# GSM.net
KiCad netlist of a schematic drawn in Altium Designer
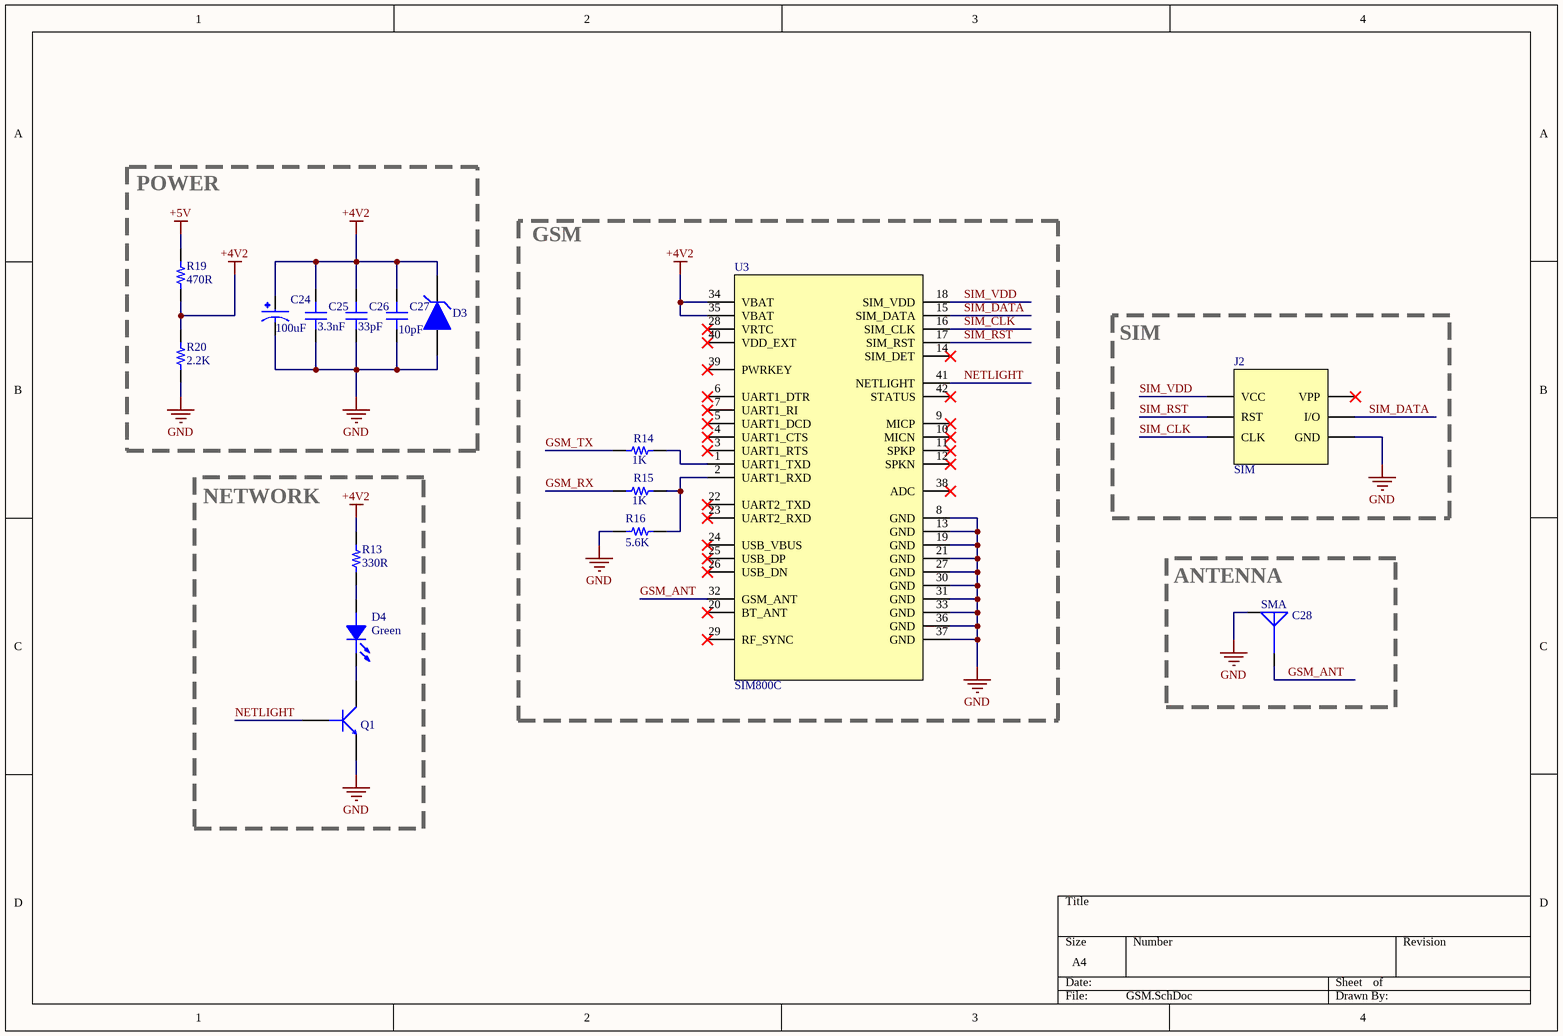
[diagram p0: GSM.SchDoc]

(export (version "E")
  (design (tool "Eeschema 10.0.6"))
  (components
    (comp (ref "C24")
      (value "100uF")
      (footprint "TANTAL B-CASE")
      (description "TANTAL")
      (libsource (lib "hava_kalitesi_olcumu") (part "100uF"))
    )
    (comp (ref "C25")
      (value "3.3nF")
      (footprint "CAP 0603_1608")
      (description "CERAMİC 1206 SMD")
      (libsource (lib "hava_kalitesi_olcumu") (part "3.3nF"))
    )
    (comp (ref "C26")
      (value "33pF")
      (footprint "CAP 0603_1608")
      (description "CERAMİC 1206 SMD")
      (libsource (lib "hava_kalitesi_olcumu") (part "33pF"))
    )
    (comp (ref "C27")
      (value "10pF")
      (footprint "CAP 0603_1608")
      (description "CERAMİC 1206 SMD")
      (libsource (lib "hava_kalitesi_olcumu") (part "10pF"))
    )
    (comp (ref "C28")
      (value "SMA")
      (footprint "CONSMA002-G")
      (description "SMA Anten Connector")
      (libsource (lib "hava_kalitesi_olcumu") (part "Anten SMA"))
    )
    (comp (ref "D3")
      (value "ZENER DIODE")
      (footprint "SOD123")
      (description "SOD123")
      (fields
        (field (name "MANUFACTURER") "ON Semiconductor")
        (field (name "MANUFACTURER PART NUMBER") "1SMB5919BT3G")
      )
      (libsource (lib "hava_kalitesi_olcumu") (part "ZENER DIODE"))
    )
    (comp (ref "D4")
      (value "Green")
      (footprint "0805 Green LED")
      (fields
        (field (name "MANUFACTURER") "AVAGO Technologies")
        (field (name "VOLTAGE") "2.2V")
        (field (name "Comment") "0805 Green LED")
      )
      (libsource (lib "hava_kalitesi_olcumu") (part "0805 Green LED"))
    )
    (comp (ref "J2")
      (value "SIM")
      (footprint "GCT_SIM7100-6-1-15-00-A_REVC")
      (description "Memory Card Connectors Micro SIM Card Connector - Push-Push Type, 6 Pin, SMT, 1.50mm Profile")
      (fields (field (name "MP") "SIM7100-6-1-15-00-A") (field (name "MF") "Global Connector Technology"))
      (libsource (lib "hava_kalitesi_olcumu") (part "SIM7100-6-1-15-00-A"))
    )
    (comp (ref "Q1")
      (value "MMBT3904-7-F")
      (footprint "SOT-23F")
      (description "Transistor General Purpose BJT NPN 40 Volt 0.2A Automotive 3-Pin SOT-23")
      (fields (field (name "MANUFACTURER") "Diodes Zetex") (field (name "DESIGNED BY") "BERK"))
      (libsource (lib "hava_kalitesi_olcumu") (part "MMBT3904-7-F"))
    )
    (comp (ref "R13")
      (value "330R")
      (footprint "RES 0603_1608")
      (description "SMT RES 1206")
      (libsource (lib "hava_kalitesi_olcumu") (part "330R"))
    )
    (comp (ref "R14")
      (value "1K")
      (footprint "RES 0603_1608")
      (description "SMT RES 1206")
      (libsource (lib "hava_kalitesi_olcumu") (part "1K"))
    )
    (comp (ref "R15")
      (value "1K")
      (footprint "RES 0603_1608")
      (description "SMT RES 1206")
      (libsource (lib "hava_kalitesi_olcumu") (part "1K"))
    )
    (comp (ref "R16")
      (value "5.6K")
      (footprint "RES 0603_1608")
      (description "SMT RES 1206")
      (libsource (lib "hava_kalitesi_olcumu") (part "5.6K"))
    )
    (comp (ref "R19")
      (value "470R")
      (footprint "RES 0603_1608")
      (description "SMT RES 1206")
      (libsource (lib "hava_kalitesi_olcumu") (part "470R"))
    )
    (comp (ref "R20")
      (value "2.2K")
      (footprint "RES 0603_1608")
      (description "SMT RES 1206")
      (libsource (lib "hava_kalitesi_olcumu") (part "2.2K"))
    )
    (comp (ref "U3")
      (value "SIM800C")
      (footprint "LCC110P1570X1760X250-42N")
      (description "GSM/Bluetooth")
      (libsource (lib "hava_kalitesi_olcumu") (part "SIM800C"))
    )
  )
  (nets
    (net (code "1") (name "+4V2") (class "Default")
      (node (ref "C24") (pin "+") (pinfunction "+_+") (pintype "passive"))
      (node (ref "C25") (pin "2") (pinfunction "2_2") (pintype "passive"))
      (node (ref "C26") (pin "2") (pinfunction "2_2") (pintype "passive"))
      (node (ref "C27") (pin "2") (pinfunction "2_2") (pintype "passive"))
      (node (ref "D3") (pin "C") (pinfunction "C_C") (pintype "passive"))
      (node (ref "R13") (pin "2") (pinfunction "2_2") (pintype "passive"))
      (node (ref "R19") (pin "1") (pinfunction "1_1") (pintype "passive"))
      (node (ref "R20") (pin "2") (pinfunction "2_2") (pintype "passive"))
      (node (ref "U3") (pin "34") (pinfunction "VBAT_34") (pintype "power_in"))
      (node (ref "U3") (pin "35") (pinfunction "VBAT_35") (pintype "power_in"))
    )
    (net (code "2") (name "+5V") (class "Default")
      (node (ref "R19") (pin "2") (pinfunction "2_2") (pintype "passive"))
    )
    (net (code "3") (name "/GSM_ANT") (class "Default")
      (node (ref "C28") (pin "S") (pinfunction "S_S") (pintype "passive"))
      (node (ref "U3") (pin "32") (pinfunction "GSM_ANT_32") (pintype "power_in"))
    )
    (net (code "4") (name "/GSM_RX") (class "Default")
      (node (ref "R15") (pin "1") (pinfunction "1_1") (pintype "passive"))
    )
    (net (code "5") (name "/GSM_TX") (class "Default")
      (node (ref "R14") (pin "1") (pinfunction "1_1") (pintype "passive"))
    )
    (net (code "6") (name "/NETLIGHT") (class "Default")
      (node (ref "Q1") (pin "1") (pinfunction "B_1") (pintype "power_in"))
      (node (ref "U3") (pin "41") (pinfunction "NETLIGHT_41") (pintype "power_in"))
    )
    (net (code "7") (name "/SIM_CLK") (class "Default")
      (node (ref "J2") (pin "C3") (pinfunction "CLK_C3") (pintype "power_in"))
      (node (ref "U3") (pin "16") (pinfunction "SIM_CLK_16") (pintype "power_in"))
    )
    (net (code "8") (name "/SIM_DATA") (class "Default")
      (node (ref "J2") (pin "C7") (pinfunction "I/O_C7") (pintype "power_in"))
      (node (ref "U3") (pin "15") (pinfunction "SIM_DATA_15") (pintype "power_in"))
    )
    (net (code "9") (name "/SIM_RST") (class "Default")
      (node (ref "J2") (pin "C2") (pinfunction "RST_C2") (pintype "power_in"))
      (node (ref "U3") (pin "17") (pinfunction "SIM_RST_17") (pintype "power_in"))
    )
    (net (code "10") (name "/SIM_VDD") (class "Default")
      (node (ref "J2") (pin "C1") (pinfunction "VCC_C1") (pintype "power_in"))
      (node (ref "U3") (pin "18") (pinfunction "SIM_VDD_18") (pintype "power_in"))
    )
    (net (code "11") (name "GND") (class "Default")
      (node (ref "C24") (pin "-") (pinfunction "-_-") (pintype "passive"))
      (node (ref "C25") (pin "1") (pinfunction "1_1") (pintype "passive"))
      (node (ref "C26") (pin "1") (pinfunction "1_1") (pintype "passive"))
      (node (ref "C27") (pin "1") (pinfunction "1_1") (pintype "passive"))
      (node (ref "C28") (pin "G") (pinfunction "G_G") (pintype "passive"))
      (node (ref "D3") (pin "A") (pinfunction "A_A") (pintype "passive"))
      (node (ref "J2") (pin "C5") (pinfunction "GND_C5") (pintype "power_in"))
      (node (ref "Q1") (pin "2") (pinfunction "E_2") (pintype "power_in"))
      (node (ref "R16") (pin "1") (pinfunction "1_1") (pintype "passive"))
      (node (ref "R20") (pin "1") (pinfunction "1_1") (pintype "passive"))
      (node (ref "U3") (pin "13") (pinfunction "GND_13") (pintype "power_in"))
      (node (ref "U3") (pin "19") (pinfunction "GND_19") (pintype "power_in"))
      (node (ref "U3") (pin "21") (pinfunction "GND_21") (pintype "power_in"))
      (node (ref "U3") (pin "27") (pinfunction "GND_27") (pintype "power_in"))
      (node (ref "U3") (pin "30") (pinfunction "GND_30") (pintype "power_in"))
      (node (ref "U3") (pin "31") (pinfunction "GND_31") (pintype "power_in"))
      (node (ref "U3") (pin "33") (pinfunction "GND_33") (pintype "power_in"))
      (node (ref "U3") (pin "36") (pinfunction "GND_36") (pintype "power_in"))
      (node (ref "U3") (pin "37") (pinfunction "GND_37") (pintype "power_in"))
      (node (ref "U3") (pin "8") (pinfunction "GND_8") (pintype "power_in"))
    )
    (net (code "12") (name "Net-(D4-ANODE)") (class "Default")
      (node (ref "D4") (pin "1") (pinfunction "ANODE_1") (pintype "passive"))
      (node (ref "R13") (pin "1") (pinfunction "1_1") (pintype "passive"))
    )
    (net (code "13") (name "Net-(D4-CATHODE)") (class "Default")
      (node (ref "D4") (pin "2") (pinfunction "CATHODE_2") (pintype "passive"))
      (node (ref "Q1") (pin "3") (pinfunction "C_3") (pintype "power_in"))
    )
    (net (code "14") (name "Net-(U3-UART1_RXD)") (class "Default")
      (node (ref "R15") (pin "2") (pinfunction "2_2") (pintype "passive"))
      (node (ref "R16") (pin "2") (pinfunction "2_2") (pintype "passive"))
      (node (ref "U3") (pin "2") (pinfunction "UART1_RXD_2") (pintype "power_in"))
    )
    (net (code "15") (name "Net-(U3-UART1_TXD)") (class "Default")
      (node (ref "R14") (pin "2") (pinfunction "2_2") (pintype "passive"))
      (node (ref "U3") (pin "1") (pinfunction "UART1_TXD_1") (pintype "power_in"))
    )
    (net (code "16") (name "unconnected-(J2-VPP-PadC6)") (class "Default")
      (node (ref "J2") (pin "C6") (pinfunction "VPP_C6") (pintype "power_in+no_connect"))
    )
    (net (code "17") (name "unconnected-(U3-ADC-Pad38)") (class "Default")
      (node (ref "U3") (pin "38") (pinfunction "ADC_38") (pintype "power_in+no_connect"))
    )
    (net (code "18") (name "unconnected-(U3-BT_ANT-Pad20)") (class "Default")
      (node (ref "U3") (pin "20") (pinfunction "BT_ANT_20") (pintype "power_in+no_connect"))
    )
    (net (code "19") (name "unconnected-(U3-MICN-Pad10)") (class "Default")
      (node (ref "U3") (pin "10") (pinfunction "MICN_10") (pintype "power_in+no_connect"))
    )
    (net (code "20") (name "unconnected-(U3-MICP-Pad9)") (class "Default")
      (node (ref "U3") (pin "9") (pinfunction "MICP_9") (pintype "power_in+no_connect"))
    )
    (net (code "21") (name "unconnected-(U3-PWRKEY-Pad39)") (class "Default")
      (node (ref "U3") (pin "39") (pinfunction "PWRKEY_39") (pintype "power_in+no_connect"))
    )
    (net (code "22") (name "unconnected-(U3-RF_SYNC-Pad29)") (class "Default")
      (node (ref "U3") (pin "29") (pinfunction "RF_SYNC_29") (pintype "power_in+no_connect"))
    )
    (net (code "23") (name "unconnected-(U3-SIM_DET-Pad14)") (class "Default")
      (node (ref "U3") (pin "14") (pinfunction "SIM_DET_14") (pintype "power_in+no_connect"))
    )
    (net (code "24") (name "unconnected-(U3-SPKN-Pad12)") (class "Default")
      (node (ref "U3") (pin "12") (pinfunction "SPKN_12") (pintype "power_in+no_connect"))
    )
    (net (code "25") (name "unconnected-(U3-SPKP-Pad11)") (class "Default")
      (node (ref "U3") (pin "11") (pinfunction "SPKP_11") (pintype "power_in+no_connect"))
    )
    (net (code "26") (name "unconnected-(U3-STATUS-Pad42)") (class "Default")
      (node (ref "U3") (pin "42") (pinfunction "STATUS_42") (pintype "power_in+no_connect"))
    )
    (net (code "27") (name "unconnected-(U3-UART1_CTS-Pad4)") (class "Default")
      (node (ref "U3") (pin "4") (pinfunction "UART1_CTS_4") (pintype "power_in+no_connect"))
    )
    (net (code "28") (name "unconnected-(U3-UART1_DCD-Pad5)") (class "Default")
      (node (ref "U3") (pin "5") (pinfunction "UART1_DCD_5") (pintype "power_in+no_connect"))
    )
    (net (code "29") (name "unconnected-(U3-UART1_DTR-Pad6)") (class "Default")
      (node (ref "U3") (pin "6") (pinfunction "UART1_DTR_6") (pintype "power_in+no_connect"))
    )
    (net (code "30") (name "unconnected-(U3-UART1_RI-Pad7)") (class "Default")
      (node (ref "U3") (pin "7") (pinfunction "UART1_RI_7") (pintype "power_in+no_connect"))
    )
    (net (code "31") (name "unconnected-(U3-UART1_RTS-Pad3)") (class "Default")
      (node (ref "U3") (pin "3") (pinfunction "UART1_RTS_3") (pintype "power_in+no_connect"))
    )
    (net (code "32") (name "unconnected-(U3-UART2_RXD-Pad23)") (class "Default")
      (node (ref "U3") (pin "23") (pinfunction "UART2_RXD_23") (pintype "power_in+no_connect"))
    )
    (net (code "33") (name "unconnected-(U3-UART2_TXD-Pad22)") (class "Default")
      (node (ref "U3") (pin "22") (pinfunction "UART2_TXD_22") (pintype "power_in+no_connect"))
    )
    (net (code "34") (name "unconnected-(U3-USB_DN-Pad26)") (class "Default")
      (node (ref "U3") (pin "26") (pinfunction "USB_DN_26") (pintype "power_in+no_connect"))
    )
    (net (code "35") (name "unconnected-(U3-USB_DP-Pad25)") (class "Default")
      (node (ref "U3") (pin "25") (pinfunction "USB_DP_25") (pintype "power_in+no_connect"))
    )
    (net (code "36") (name "unconnected-(U3-USB_VBUS-Pad24)") (class "Default")
      (node (ref "U3") (pin "24") (pinfunction "USB_VBUS_24") (pintype "power_in+no_connect"))
    )
    (net (code "37") (name "unconnected-(U3-VDD_EXT-Pad40)") (class "Default")
      (node (ref "U3") (pin "40") (pinfunction "VDD_EXT_40") (pintype "power_in+no_connect"))
    )
    (net (code "38") (name "unconnected-(U3-VRTC-Pad28)") (class "Default")
      (node (ref "U3") (pin "28") (pinfunction "VRTC_28") (pintype "power_in+no_connect"))
    )
  )
)
